# HLib-Comm-XBee.net
KiCad netlist of a schematic drawn in Altium Designer
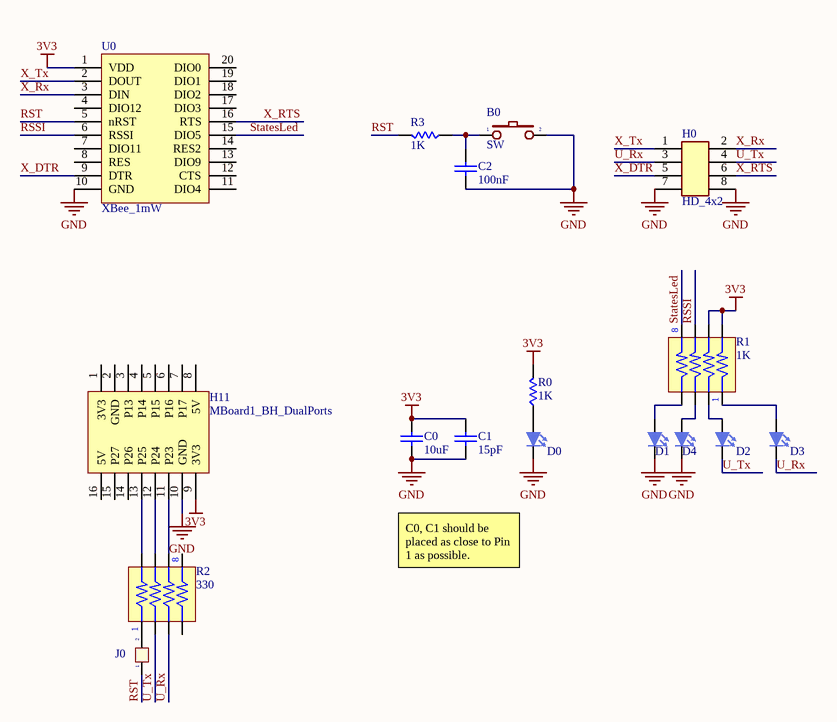
[diagram p0: HLib-Comm-XBee.SchDoc]

(export (version "E")
  (design (tool "Eeschema 10.0.6"))
  (components
    (comp (ref "B0")
      (value "SW")
      (footprint "SW2SMD")
      (description "Switch button 2 pin")
      (libsource (lib "syhaunguyen") (part "SW2"))
    )
    (comp (ref "C0")
      (value "10uF")
      (footprint "SM_0805_C_CERAMIC")
      (description "Non-polarity ceramic capacitor")
      (fields (field (name "Comment") "C_Ceramic") (field (name "PUBLISHER") "Altium Limited"))
      (libsource (lib "HLib_discrete_sch") (part "C_Ceramic"))
    )
    (comp (ref "C1")
      (value "15pF")
      (footprint "SM_0805_C_CERAMIC")
      (description "Non-polarity ceramic capacitor")
      (fields (field (name "Comment") "C_Ceramic") (field (name "PUBLISHER") "Altium Limited"))
      (libsource (lib "HLib_discrete_sch") (part "C_Ceramic"))
    )
    (comp (ref "C2")
      (value "100nF")
      (footprint "SM_0805_C_CERAMIC")
      (description "Non-polarity ceramic capacitor")
      (fields (field (name "Comment") "C_Ceramic") (field (name "PUBLISHER") "Altium Limited"))
      (libsource (lib "HLib_discrete_sch") (part "C_Ceramic"))
    )
    (comp (ref "D0")
      (value "LED")
      (footprint "SM_0805_LED")
      (fields (field (name "PUBLISHER") "Altium Limited"))
      (libsource (lib "HLib_discrete_sch") (part "LED"))
    )
    (comp (ref "D1")
      (value "LED")
      (footprint "SM_0805_LED")
      (fields (field (name "PUBLISHER") "Altium Limited"))
      (libsource (lib "HLib_discrete_sch") (part "LED"))
    )
    (comp (ref "D2")
      (value "LED")
      (footprint "SM_0805_LED")
      (fields (field (name "PUBLISHER") "Altium Limited"))
      (libsource (lib "HLib_discrete_sch") (part "LED"))
    )
    (comp (ref "D3")
      (value "LED")
      (footprint "SM_0805_LED")
      (fields (field (name "PUBLISHER") "Altium Limited"))
      (libsource (lib "HLib_discrete_sch") (part "LED"))
    )
    (comp (ref "D4")
      (value "LED")
      (footprint "SM_0805_LED")
      (fields (field (name "PUBLISHER") "Altium Limited"))
      (libsource (lib "HLib_discrete_sch") (part "LED"))
    )
    (comp (ref "H0")
      (value "HD_4x2")
      (footprint "HD_male_4x2_100mil_straight")
      (description "Header, 4-pins/row, double row,")
      (libsource (lib "HLib_connector_sch") (part "HD_4x2"))
    )
    (comp (ref "H11")
      (value "MBoard1_BH_DualPorts")
      (footprint "MBoard1_BH_DualPorts")
      (libsource (lib "Nhat_Lib") (part "MBoard1_BH_DualPorts"))
    )
    (comp (ref "J0") (value "Jumper 2") (footprint "J2") (libsource (lib "VioletofSun") (part "JP 2")))
    (comp (ref "R0")
      (value "1K")
      (footprint "SM_0805_R")
      (description "Resistor")
      (fields (field (name "Comment") "R") (field (name "PUBLISHER") "Altium Limited"))
      (libsource (lib "HLib_discrete_sch") (part "R"))
    )
    (comp (ref "R1") (value "1K") (footprint "RA4") (libsource (lib "Nhat_Lib") (part "RA4")))
    (comp (ref "R2") (value "330") (footprint "RA4") (libsource (lib "") (part "RA4_1")))
    (comp (ref "R3")
      (value "1K")
      (footprint "SM_0805_R")
      (description "Resistor")
      (fields (field (name "Comment") "R") (field (name "PUBLISHER") "Altium Limited"))
      (libsource (lib "HLib_discrete_sch") (part "R"))
    )
    (comp (ref "U0") (value "XBee_1mW") (footprint "XBee") (libsource (lib "Nhat_Lib") (part "XBee_1mW")))
  )
  (nets
    (net (code "1") (name "/RSSI") (class "Default")
      (node (ref "R1") (pin "6") (pinfunction "6_6") (pintype "passive"))
      (node (ref "U0") (pin "6") (pinfunction "RSSI_6") (pintype "passive"))
    )
    (net (code "2") (name "/RST") (class "Default")
      (node (ref "J0") (pin "1") (pinfunction "1_1") (pintype "passive"))
      (node (ref "R3") (pin "2") (pinfunction "2_2") (pintype "passive"))
      (node (ref "U0") (pin "5") (pinfunction "nRST_5") (pintype "passive"))
    )
    (net (code "3") (name "/StatesLed") (class "Default")
      (node (ref "R1") (pin "8") (pinfunction "8_8") (pintype "passive"))
      (node (ref "U0") (pin "15") (pinfunction "DIO5_15") (pintype "passive"))
    )
    (net (code "4") (name "/U_Rx") (class "Default")
      (node (ref "D3") (pin "2") (pinfunction "K_2") (pintype "passive"))
      (node (ref "H0") (pin "3") (pinfunction "3_3") (pintype "passive"))
      (node (ref "R2") (pin "5") (pinfunction "5_5") (pintype "passive"))
    )
    (net (code "5") (name "/U_Tx") (class "Default")
      (node (ref "D2") (pin "2") (pinfunction "K_2") (pintype "passive"))
      (node (ref "H0") (pin "4") (pinfunction "4_4") (pintype "passive"))
      (node (ref "R2") (pin "3") (pinfunction "3_3") (pintype "passive"))
    )
    (net (code "6") (name "/X_DTR") (class "Default")
      (node (ref "H0") (pin "5") (pinfunction "5_5") (pintype "passive"))
      (node (ref "U0") (pin "9") (pinfunction "DTR_9") (pintype "passive"))
    )
    (net (code "7") (name "/X_RTS") (class "Default")
      (node (ref "H0") (pin "6") (pinfunction "6_6") (pintype "passive"))
      (node (ref "U0") (pin "16") (pinfunction "RTS_16") (pintype "passive"))
    )
    (net (code "8") (name "/X_Rx") (class "Default")
      (node (ref "H0") (pin "2") (pinfunction "2_2") (pintype "passive"))
      (node (ref "U0") (pin "3") (pinfunction "DIN_3") (pintype "passive"))
    )
    (net (code "9") (name "/X_Tx") (class "Default")
      (node (ref "H0") (pin "1") (pinfunction "1_1") (pintype "passive"))
      (node (ref "U0") (pin "2") (pinfunction "DOUT_2") (pintype "passive"))
    )
    (net (code "10") (name "3V3") (class "Default")
      (node (ref "C0") (pin "2") (pinfunction "2_2") (pintype "passive"))
      (node (ref "C1") (pin "2") (pinfunction "2_2") (pintype "passive"))
      (node (ref "H11") (pin "9") (pinfunction "3V3_9") (pintype "passive"))
      (node (ref "R0") (pin "2") (pinfunction "2_2") (pintype "passive"))
      (node (ref "R1") (pin "2") (pinfunction "2_2") (pintype "passive"))
      (node (ref "R1") (pin "4") (pinfunction "4_4") (pintype "passive"))
      (node (ref "U0") (pin "1") (pinfunction "VDD_1") (pintype "passive"))
    )
    (net (code "11") (name "GND") (class "Default")
      (node (ref "B0") (pin "2") (pinfunction "2_2") (pintype "passive"))
      (node (ref "C0") (pin "1") (pinfunction "1_1") (pintype "passive"))
      (node (ref "C1") (pin "1") (pinfunction "1_1") (pintype "passive"))
      (node (ref "C2") (pin "1") (pinfunction "1_1") (pintype "passive"))
      (node (ref "D0") (pin "2") (pinfunction "K_2") (pintype "passive"))
      (node (ref "D1") (pin "2") (pinfunction "K_2") (pintype "passive"))
      (node (ref "D4") (pin "2") (pinfunction "K_2") (pintype "passive"))
      (node (ref "H0") (pin "7") (pinfunction "7_7") (pintype "passive"))
      (node (ref "H0") (pin "8") (pinfunction "8_8") (pintype "passive"))
      (node (ref "H11") (pin "10") (pinfunction "GND_10") (pintype "passive"))
      (node (ref "U0") (pin "10") (pinfunction "GND_10") (pintype "passive"))
    )
    (net (code "12") (name "Net-(B0-Pad1)") (class "Default")
      (node (ref "B0") (pin "1") (pinfunction "1_1") (pintype "passive"))
      (node (ref "C2") (pin "2") (pinfunction "2_2") (pintype "passive"))
      (node (ref "R3") (pin "1") (pinfunction "1_1") (pintype "passive"))
    )
    (net (code "13") (name "Net-(D0-A)") (class "Default")
      (node (ref "D0") (pin "1") (pinfunction "A_1") (pintype "passive"))
      (node (ref "R0") (pin "1") (pinfunction "1_1") (pintype "passive"))
    )
    (net (code "14") (name "Net-(D1-A)") (class "Default")
      (node (ref "D1") (pin "1") (pinfunction "A_1") (pintype "passive"))
      (node (ref "R1") (pin "7") (pinfunction "7_7") (pintype "passive"))
    )
    (net (code "15") (name "Net-(D2-A)") (class "Default")
      (node (ref "D2") (pin "1") (pinfunction "A_1") (pintype "passive"))
      (node (ref "R1") (pin "3") (pinfunction "3_3") (pintype "passive"))
    )
    (net (code "16") (name "Net-(D3-A)") (class "Default")
      (node (ref "D3") (pin "1") (pinfunction "A_1") (pintype "passive"))
      (node (ref "R1") (pin "1") (pinfunction "1_1") (pintype "passive"))
    )
    (net (code "17") (name "Net-(D4-A)") (class "Default")
      (node (ref "D4") (pin "1") (pinfunction "A_1") (pintype "passive"))
      (node (ref "R1") (pin "5") (pinfunction "5_5") (pintype "passive"))
    )
    (net (code "18") (name "Net-(H11-P23)") (class "Default")
      (node (ref "H11") (pin "11") (pinfunction "P23_11") (pintype "passive"))
      (node (ref "R2") (pin "6") (pinfunction "6_6") (pintype "passive"))
    )
    (net (code "19") (name "Net-(H11-P24)") (class "Default")
      (node (ref "H11") (pin "12") (pinfunction "P24_12") (pintype "passive"))
      (node (ref "R2") (pin "4") (pinfunction "4_4") (pintype "passive"))
    )
    (net (code "20") (name "Net-(H11-P25)") (class "Default")
      (node (ref "H11") (pin "13") (pinfunction "P25_13") (pintype "passive"))
      (node (ref "R2") (pin "2") (pinfunction "2_2") (pintype "passive"))
    )
    (net (code "21") (name "Net-(J0-Pad2)") (class "Default")
      (node (ref "J0") (pin "2") (pinfunction "2_2") (pintype "passive"))
      (node (ref "R2") (pin "1") (pinfunction "1_1") (pintype "passive"))
    )
    (net (code "22") (name "unconnected-(H11-3V3-Pad1)") (class "Default")
      (node (ref "H11") (pin "1") (pinfunction "3V3_1") (pintype "passive"))
    )
    (net (code "23") (name "unconnected-(H11-5V-Pad8)") (class "Default")
      (node (ref "H11") (pin "8") (pinfunction "5V_8") (pintype "passive"))
    )
    (net (code "24") (name "unconnected-(H11-5V-Pad16)") (class "Default")
      (node (ref "H11") (pin "16") (pinfunction "5V_16") (pintype "passive"))
    )
    (net (code "25") (name "unconnected-(H11-GND-Pad2)") (class "Default")
      (node (ref "H11") (pin "2") (pinfunction "GND_2") (pintype "passive"))
    )
    (net (code "26") (name "unconnected-(H11-P13-Pad3)") (class "Default")
      (node (ref "H11") (pin "3") (pinfunction "P13_3") (pintype "passive"))
    )
    (net (code "27") (name "unconnected-(H11-P14-Pad4)") (class "Default")
      (node (ref "H11") (pin "4") (pinfunction "P14_4") (pintype "passive"))
    )
    (net (code "28") (name "unconnected-(H11-P15-Pad5)") (class "Default")
      (node (ref "H11") (pin "5") (pinfunction "P15_5") (pintype "passive"))
    )
    (net (code "29") (name "unconnected-(H11-P16-Pad6)") (class "Default")
      (node (ref "H11") (pin "6") (pinfunction "P16_6") (pintype "passive"))
    )
    (net (code "30") (name "unconnected-(H11-P17-Pad7)") (class "Default")
      (node (ref "H11") (pin "7") (pinfunction "P17_7") (pintype "passive"))
    )
    (net (code "31") (name "unconnected-(H11-P26-Pad14)") (class "Default")
      (node (ref "H11") (pin "14") (pinfunction "P26_14") (pintype "passive"))
    )
    (net (code "32") (name "unconnected-(H11-P27-Pad15)") (class "Default")
      (node (ref "H11") (pin "15") (pinfunction "P27_15") (pintype "passive"))
    )
    (net (code "33") (name "unconnected-(R2-Pad7)") (class "Default")
      (node (ref "R2") (pin "7") (pinfunction "7_7") (pintype "passive"))
    )
    (net (code "34") (name "unconnected-(R2-Pad8)") (class "Default")
      (node (ref "R2") (pin "8") (pinfunction "8_8") (pintype "passive"))
    )
    (net (code "35") (name "unconnected-(U0-CTS-Pad12)") (class "Default")
      (node (ref "U0") (pin "12") (pinfunction "CTS_12") (pintype "passive"))
    )
    (net (code "36") (name "unconnected-(U0-DIO0-Pad20)") (class "Default")
      (node (ref "U0") (pin "20") (pinfunction "DIO0_20") (pintype "passive"))
    )
    (net (code "37") (name "unconnected-(U0-DIO1-Pad19)") (class "Default")
      (node (ref "U0") (pin "19") (pinfunction "DIO1_19") (pintype "passive"))
    )
    (net (code "38") (name "unconnected-(U0-DIO2-Pad18)") (class "Default")
      (node (ref "U0") (pin "18") (pinfunction "DIO2_18") (pintype "passive"))
    )
    (net (code "39") (name "unconnected-(U0-DIO3-Pad17)") (class "Default")
      (node (ref "U0") (pin "17") (pinfunction "DIO3_17") (pintype "passive"))
    )
    (net (code "40") (name "unconnected-(U0-DIO4-Pad11)") (class "Default")
      (node (ref "U0") (pin "11") (pinfunction "DIO4_11") (pintype "passive"))
    )
    (net (code "41") (name "unconnected-(U0-DIO9-Pad13)") (class "Default")
      (node (ref "U0") (pin "13") (pinfunction "DIO9_13") (pintype "passive"))
    )
    (net (code "42") (name "unconnected-(U0-DIO11-Pad7)") (class "Default")
      (node (ref "U0") (pin "7") (pinfunction "DIO11_7") (pintype "passive"))
    )
    (net (code "43") (name "unconnected-(U0-DIO12-Pad4)") (class "Default")
      (node (ref "U0") (pin "4") (pinfunction "DIO12_4") (pintype "passive"))
    )
    (net (code "44") (name "unconnected-(U0-RES-Pad8)") (class "Default")
      (node (ref "U0") (pin "8") (pinfunction "RES_8") (pintype "passive"))
    )
    (net (code "45") (name "unconnected-(U0-RES2-Pad14)") (class "Default")
      (node (ref "U0") (pin "14") (pinfunction "RES2_14") (pintype "passive"))
    )
  )
)
